# music_badge_v1_2_2017-09-16.net
KiCad netlist of a schematic drawn in EAGLE
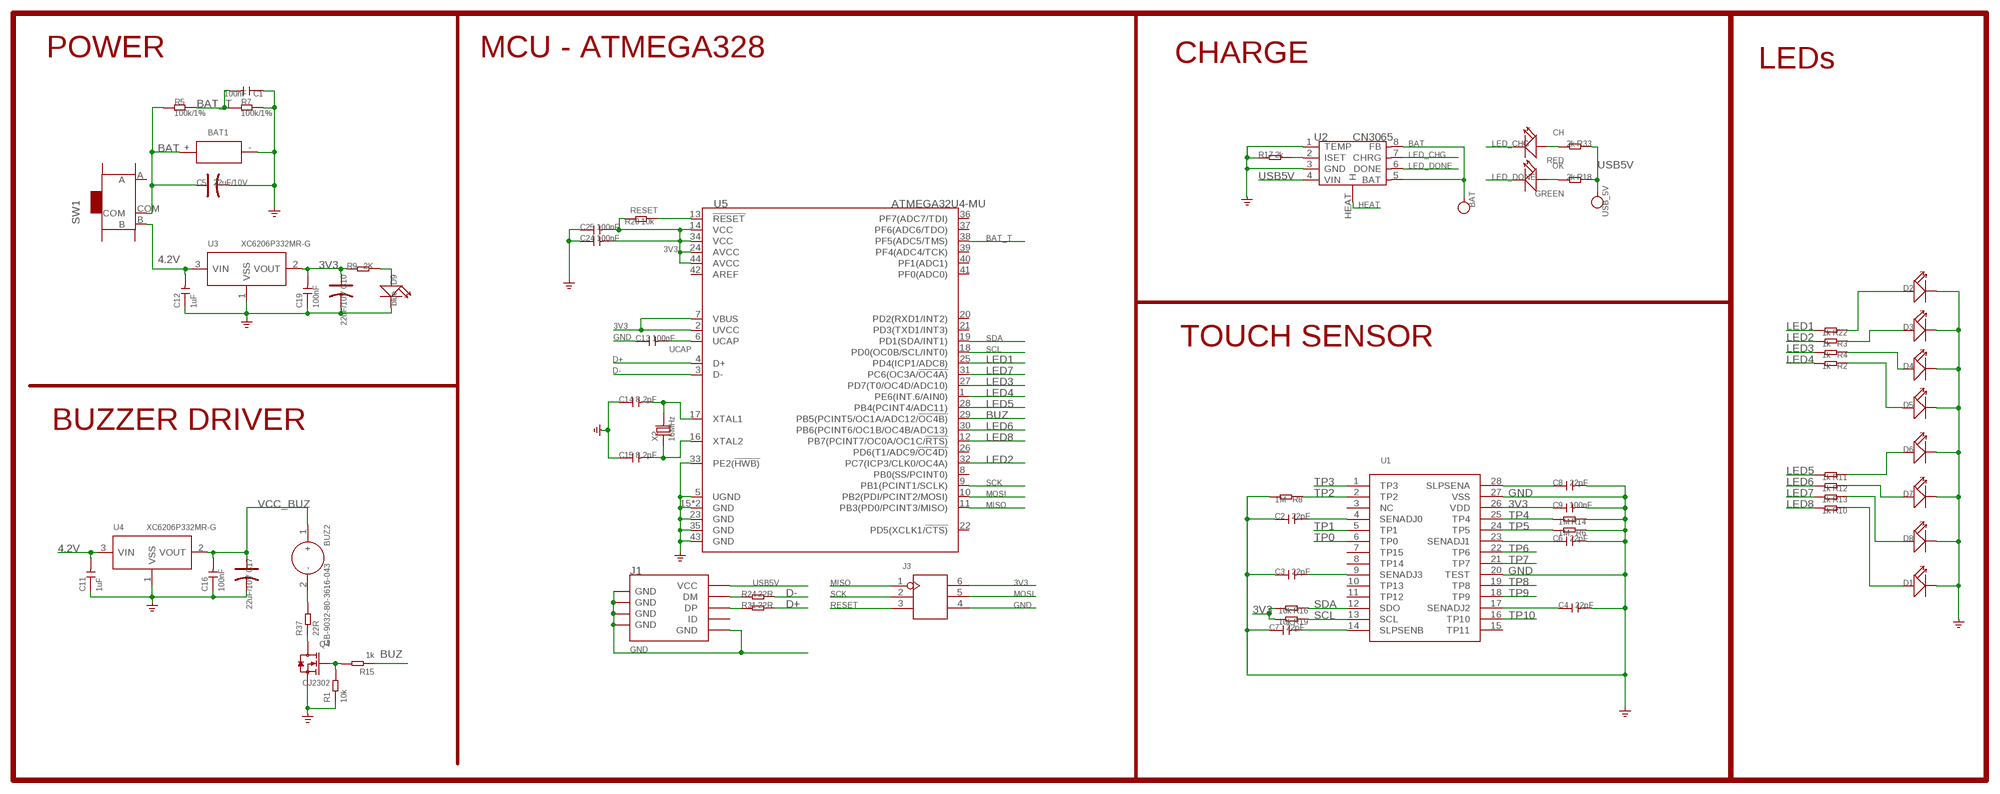
[diagram p0: schematic, sheet 1]

(export (version "E")
  (design (tool "Eeschema 10.0.6"))
  (components
    (comp (ref "BAT")
      (value "TEST-POINT-35")
      (footprint "eagle-import:TP_3535")
      (libsource (lib "eagle-import") (part "TEST-POINT-35"))
    )
    (comp (ref "BAT1")
      (value "HOLDER-BATTERY")
      (footprint "eagle-import:2P-SMD-L28.5_W16_H5.5")
      (libsource (lib "eagle-import") (part "HOLDER-BATTERY"))
    )
    (comp (ref "BUZ2")
      (value "GB-9032-80-3616-043")
      (footprint "eagle-import:BZ2-SMD-9X10.6X3.2MM")
      (libsource (lib "eagle-import") (part "BUZZER-9X3.2MM"))
    )
    (comp (ref "C1")
      (value "100nF")
      (footprint "eagle-import:C0603")
      (libsource (lib "eagle-import") (part "C-0603"))
    )
    (comp (ref "C2")
      (value "22pF")
      (footprint "eagle-import:C0603")
      (libsource (lib "eagle-import") (part "C-0603"))
    )
    (comp (ref "C3")
      (value "22pF")
      (footprint "eagle-import:C0603")
      (libsource (lib "eagle-import") (part "C-0603"))
    )
    (comp (ref "C4")
      (value "22pF")
      (footprint "eagle-import:C0603")
      (libsource (lib "eagle-import") (part "C-0603"))
    )
    (comp (ref "C5")
      (value "22uF/10V")
      (footprint "eagle-import:AVX-B")
      (libsource (lib "eagle-import") (part "CAP-AVX-B"))
    )
    (comp (ref "C6")
      (value "22pF")
      (footprint "eagle-import:C0603")
      (libsource (lib "eagle-import") (part "C-0603"))
    )
    (comp (ref "C7")
      (value "22pF")
      (footprint "eagle-import:C0603")
      (libsource (lib "eagle-import") (part "C-0603"))
    )
    (comp (ref "C8")
      (value "22pF")
      (footprint "eagle-import:C0603")
      (libsource (lib "eagle-import") (part "C-0603"))
    )
    (comp (ref "C9")
      (value "100nF")
      (footprint "eagle-import:C0603")
      (libsource (lib "eagle-import") (part "C-0603"))
    )
    (comp (ref "C10")
      (value "22uF/10V")
      (footprint "eagle-import:AVX-B")
      (libsource (lib "eagle-import") (part "CAP-AVX-B"))
    )
    (comp (ref "C11")
      (value "1uF")
      (footprint "eagle-import:C0603")
      (libsource (lib "eagle-import") (part "CAP-0603"))
    )
    (comp (ref "C12")
      (value "1uF")
      (footprint "eagle-import:C0603")
      (libsource (lib "eagle-import") (part "CAP-0603"))
    )
    (comp (ref "C13")
      (value "100nF")
      (footprint "eagle-import:C0603")
      (libsource (lib "eagle-import") (part "C-0603"))
    )
    (comp (ref "C14")
      (value "8.2pF")
      (footprint "eagle-import:C0603")
      (libsource (lib "eagle-import") (part "C-0603"))
    )
    (comp (ref "C15")
      (value "8.2pF")
      (footprint "eagle-import:C0603")
      (libsource (lib "eagle-import") (part "C-0603"))
    )
    (comp (ref "C16")
      (value "100nF")
      (footprint "eagle-import:C0603")
      (libsource (lib "eagle-import") (part "CAP-0603"))
    )
    (comp (ref "C17")
      (value "22uF/10V")
      (footprint "eagle-import:AVX-B")
      (libsource (lib "eagle-import") (part "CAP-AVX-B"))
    )
    (comp (ref "C19")
      (value "100nF")
      (footprint "eagle-import:C0603")
      (libsource (lib "eagle-import") (part "CAP-0603"))
    )
    (comp (ref "C24")
      (value "100nF")
      (footprint "eagle-import:C0603")
      (libsource (lib "eagle-import") (part "C-0603"))
    )
    (comp (ref "C25")
      (value "100nF")
      (footprint "eagle-import:C0603")
      (libsource (lib "eagle-import") (part "C-0603"))
    )
    (comp (ref "CH")
      (value "RED")
      (footprint "eagle-import:LED-0603")
      (libsource (lib "eagle-import") (part "Discrete-new_LED'0603'"))
    )
    (comp (ref "D1")
      (value "LED-3MM")
      (footprint "eagle-import:LED-2P-2.54-3MM")
      (libsource (lib "eagle-import") (part "LED-3MM"))
    )
    (comp (ref "D2")
      (value "LED-3MM")
      (footprint "eagle-import:LED-2P-2.54-3MM")
      (libsource (lib "eagle-import") (part "LED-3MM"))
    )
    (comp (ref "D3")
      (value "LED-3MM")
      (footprint "eagle-import:LED-2P-2.54-3MM")
      (libsource (lib "eagle-import") (part "LED-3MM"))
    )
    (comp (ref "D4")
      (value "LED-3MM")
      (footprint "eagle-import:LED-2P-2.54-3MM")
      (libsource (lib "eagle-import") (part "LED-3MM"))
    )
    (comp (ref "D5")
      (value "LED-3MM")
      (footprint "eagle-import:LED-2P-2.54-3MM")
      (libsource (lib "eagle-import") (part "LED-3MM"))
    )
    (comp (ref "D6")
      (value "LED-3MM")
      (footprint "eagle-import:LED-2P-2.54-3MM")
      (libsource (lib "eagle-import") (part "LED-3MM"))
    )
    (comp (ref "D7")
      (value "LED-3MM")
      (footprint "eagle-import:LED-2P-2.54-3MM")
      (libsource (lib "eagle-import") (part "LED-3MM"))
    )
    (comp (ref "D8")
      (value "LED-3MM")
      (footprint "eagle-import:LED-2P-2.54-3MM")
      (libsource (lib "eagle-import") (part "LED-3MM"))
    )
    (comp (ref "D9")
      (value "blue")
      (footprint "eagle-import:LED-0603@1")
      (libsource (lib "eagle-import") (part "LED'0603'"))
    )
    (comp (ref "J1")
      (value "USB-MINIUSB-5P-MICRO")
      (footprint "eagle-import:MICRO-USB")
      (libsource (lib "eagle-import") (part "USB-MINIUSB-5P-MICRO"))
    )
    (comp (ref "J3")
      (value "HEADER-2X3P-2.0-1.143")
      (footprint "eagle-import:H2X3-SMD-2.0(1.143)")
      (libsource (lib "eagle-import") (part "HEADER-2X3P-2.0-1.143"))
    )
    (comp (ref "OK")
      (value "GREEN")
      (footprint "eagle-import:LED-0603")
      (libsource (lib "eagle-import") (part "Discrete-new_LED'0603'"))
    )
    (comp (ref "Q4")
      (value "CJ2302")
      (footprint "eagle-import:SOT-23")
      (libsource (lib "eagle-import") (part "MOSFET-N'SOT23'"))
    )
    (comp (ref "R1")
      (value "10k")
      (footprint "eagle-import:R0603")
      (libsource (lib "eagle-import") (part "RES-0603"))
    )
    (comp (ref "R2")
      (value "1k")
      (footprint "eagle-import:R0603")
      (libsource (lib "eagle-import") (part "R-0603"))
    )
    (comp (ref "R3")
      (value "1k")
      (footprint "eagle-import:R0603")
      (libsource (lib "eagle-import") (part "R-0603"))
    )
    (comp (ref "R4")
      (value "1k")
      (footprint "eagle-import:R0603")
      (libsource (lib "eagle-import") (part "R-0603"))
    )
    (comp (ref "R5")
      (value "100k/1%")
      (footprint "eagle-import:R0603")
      (libsource (lib "eagle-import") (part "R-0603"))
    )
    (comp (ref "R6")
      (value "1M")
      (footprint "eagle-import:R0603")
      (libsource (lib "eagle-import") (part "R-0603"))
    )
    (comp (ref "R7")
      (value "100k/1%")
      (footprint "eagle-import:R0603")
      (libsource (lib "eagle-import") (part "R-0603"))
    )
    (comp (ref "R8")
      (value "1M")
      (footprint "eagle-import:R0603")
      (libsource (lib "eagle-import") (part "R-0603"))
    )
    (comp (ref "R9")
      (value "2K")
      (footprint "eagle-import:R0603")
      (libsource (lib "eagle-import") (part "R-0603"))
    )
    (comp (ref "R10")
      (value "1k")
      (footprint "eagle-import:R0603")
      (libsource (lib "eagle-import") (part "R-0603"))
    )
    (comp (ref "R11")
      (value "1k")
      (footprint "eagle-import:R0603")
      (libsource (lib "eagle-import") (part "R-0603"))
    )
    (comp (ref "R12")
      (value "1k")
      (footprint "eagle-import:R0603")
      (libsource (lib "eagle-import") (part "R-0603"))
    )
    (comp (ref "R13")
      (value "1k")
      (footprint "eagle-import:R0603")
      (libsource (lib "eagle-import") (part "R-0603"))
    )
    (comp (ref "R14")
      (value "1M")
      (footprint "eagle-import:R0603")
      (libsource (lib "eagle-import") (part "R-0603"))
    )
    (comp (ref "R15")
      (value "1k")
      (footprint "eagle-import:R0603")
      (libsource (lib "eagle-import") (part "RES-0603"))
    )
    (comp (ref "R16")
      (value "10k")
      (footprint "eagle-import:R0603")
      (libsource (lib "eagle-import") (part "R-0603"))
    )
    (comp (ref "R17")
      (value "2k")
      (footprint "eagle-import:R0603")
      (libsource (lib "eagle-import") (part "R-0603"))
    )
    (comp (ref "R18")
      (value "2k")
      (footprint "eagle-import:R0603")
      (libsource (lib "eagle-import") (part "R-0603"))
    )
    (comp (ref "R19")
      (value "10k")
      (footprint "eagle-import:R0603")
      (libsource (lib "eagle-import") (part "R-0603"))
    )
    (comp (ref "R20")
      (value "10k")
      (footprint "eagle-import:R0603")
      (libsource (lib "eagle-import") (part "R-0603"))
    )
    (comp (ref "R22")
      (value "1k")
      (footprint "eagle-import:R0603")
      (libsource (lib "eagle-import") (part "R-0603"))
    )
    (comp (ref "R24")
      (value "22R")
      (footprint "eagle-import:R0603")
      (libsource (lib "eagle-import") (part "R-0603"))
    )
    (comp (ref "R31")
      (value "22R")
      (footprint "eagle-import:R0603")
      (libsource (lib "eagle-import") (part "R-0603"))
    )
    (comp (ref "R33")
      (value "2k")
      (footprint "eagle-import:R0603")
      (libsource (lib "eagle-import") (part "R-0603"))
    )
    (comp (ref "R37")
      (value "22R")
      (footprint "eagle-import:R0603")
      (libsource (lib "eagle-import") (part "RES-0603"))
    )
    (comp (ref "SW1")
      (value "SWITCH-3P-SMD-6.6X2.8")
      (footprint "eagle-import:3P-SMD-2CH-6.6X2.8-REINFORCE")
      (libsource (lib "eagle-import") (part "SWITCH-3P-SMD-6.6X2.8"))
    )
    (comp (ref "U1")
      (value "TTP229-BSF")
      (footprint "eagle-import:SSOP28-0.635-10X4MM")
      (libsource (lib "eagle-import") (part "TTP229-BSF"))
    )
    (comp (ref "U2")
      (value "CN3065")
      (footprint "eagle-import:DFN8")
      (libsource (lib "eagle-import") (part "CN3065-DFN8"))
    )
    (comp (ref "U3")
      (value "XC6206P332MR-G")
      (footprint "eagle-import:SOT-23")
      (libsource (lib "eagle-import") (part "PMIC-XC6206PMR"))
    )
    (comp (ref "U4")
      (value "XC6206P332MR-G")
      (footprint "eagle-import:SOT-23")
      (libsource (lib "eagle-import") (part "PMIC-XC6206PMR"))
    )
    (comp (ref "U5")
      (value "ATMEGA32U4-MU")
      (footprint "eagle-import:QFN44")
      (libsource (lib "eagle-import") (part "ATMEGA32U4-MU"))
    )
    (comp (ref "USB_5V")
      (value "TEST-POINT-35")
      (footprint "eagle-import:TP_3535")
      (libsource (lib "eagle-import") (part "TEST-POINT-35"))
    )
    (comp (ref "X2")
      (value "16MHz")
      (footprint "eagle-import:2P-SMD-5X3.2")
      (libsource (lib "eagle-import") (part "CRYSTAL'5032'"))
    )
  )
  (nets
    (net (code "1") (name "/3V3") (class "Default")
      (node (ref "C10") (pin "+") (pinfunction "+_+") (pintype "passive"))
      (node (ref "C19") (pin "2") (pinfunction "2_2") (pintype "passive"))
      (node (ref "C24") (pin "2") (pinfunction "2_2") (pintype "passive"))
      (node (ref "C25") (pin "2") (pinfunction "2_2") (pintype "passive"))
      (node (ref "C9") (pin "1") (pinfunction "1_1") (pintype "passive"))
      (node (ref "J3") (pin "6") (pinfunction "6_6") (pintype "bidirectional"))
      (node (ref "R16") (pin "2") (pinfunction "2_2") (pintype "passive"))
      (node (ref "R19") (pin "2") (pinfunction "2_2") (pintype "passive"))
      (node (ref "R20") (pin "1") (pinfunction "1_1") (pintype "passive"))
      (node (ref "R9") (pin "1") (pinfunction "1_1") (pintype "passive"))
      (node (ref "U1") (pin "26") (pinfunction "VDD_26") (pintype "bidirectional"))
      (node (ref "U3") (pin "2") (pinfunction "VOUT_2") (pintype "bidirectional"))
      (node (ref "U5") (pin "14") (pinfunction "VCC_14") (pintype "bidirectional"))
      (node (ref "U5") (pin "2") (pinfunction "UVCC_2") (pintype "bidirectional"))
      (node (ref "U5") (pin "24") (pinfunction "AVCC_24") (pintype "bidirectional"))
      (node (ref "U5") (pin "34") (pinfunction "VCC_34") (pintype "bidirectional"))
      (node (ref "U5") (pin "44") (pinfunction "AVCC_44") (pintype "bidirectional"))
      (node (ref "U5") (pin "7") (pinfunction "VBUS_7") (pintype "bidirectional"))
    )
    (net (code "2") (name "/4.2V") (class "Default")
      (node (ref "C11") (pin "2") (pinfunction "2_2") (pintype "passive"))
      (node (ref "C12") (pin "2") (pinfunction "2_2") (pintype "passive"))
      (node (ref "SW1") (pin "B") (pinfunction "B_B") (pintype "bidirectional"))
      (node (ref "U3") (pin "3") (pinfunction "VIN_3") (pintype "bidirectional"))
      (node (ref "U4") (pin "3") (pinfunction "VIN_3") (pintype "bidirectional"))
    )
    (net (code "3") (name "/BAT") (class "Default")
      (node (ref "BAT") (pin "T") (pinfunction "T_T") (pintype "bidirectional"))
      (node (ref "BAT1") (pin "+") (pinfunction "1_+") (pintype "bidirectional"))
      (node (ref "C5") (pin "+") (pinfunction "+_+") (pintype "passive"))
      (node (ref "R5") (pin "1") (pinfunction "1_1") (pintype "passive"))
      (node (ref "SW1") (pin "COM") (pinfunction "COM_COM") (pintype "bidirectional"))
      (node (ref "U2") (pin "5") (pinfunction "BAT_5") (pintype "bidirectional"))
      (node (ref "U2") (pin "8") (pinfunction "FB_8") (pintype "input"))
    )
    (net (code "4") (name "/BAT_T") (class "Default")
      (node (ref "C1") (pin "2") (pinfunction "2_2") (pintype "passive"))
      (node (ref "R5") (pin "2") (pinfunction "2_2") (pintype "passive"))
      (node (ref "R7") (pin "1") (pinfunction "1_1") (pintype "passive"))
      (node (ref "U5") (pin "38") (pinfunction "PF5(ADC5/TMS)_38") (pintype "bidirectional"))
    )
    (net (code "5") (name "/BUZ") (class "Default")
      (node (ref "R15") (pin "1") (pinfunction "1_1") (pintype "passive"))
      (node (ref "U5") (pin "29") (pinfunction "PB5(PCINT5/OC1A/ADC12/~{OC4B})_29") (pintype "bidirectional"))
    )
    (net (code "6") (name "/D+") (class "Default")
      (node (ref "R31") (pin "2") (pinfunction "2_2") (pintype "passive"))
      (node (ref "U5") (pin "4") (pinfunction "D+_4") (pintype "bidirectional"))
    )
    (net (code "7") (name "/D-") (class "Default")
      (node (ref "R24") (pin "2") (pinfunction "2_2") (pintype "passive"))
      (node (ref "U5") (pin "3") (pinfunction "D-_3") (pintype "bidirectional"))
    )
    (net (code "8") (name "/HEAT") (class "Default")
      (node (ref "U2") (pin "HEAT") (pinfunction "H_HEAT") (pintype "bidirectional"))
    )
    (net (code "9") (name "/LED1") (class "Default")
      (node (ref "R22") (pin "2") (pinfunction "2_2") (pintype "passive"))
      (node (ref "U5") (pin "25") (pinfunction "PD4(ICP1/ADC8)_25") (pintype "bidirectional"))
    )
    (net (code "10") (name "/LED2") (class "Default")
      (node (ref "R3") (pin "2") (pinfunction "2_2") (pintype "passive"))
      (node (ref "U5") (pin "32") (pinfunction "PC7(ICP3/CLK0/OC4A)_32") (pintype "bidirectional"))
    )
    (net (code "11") (name "/LED3") (class "Default")
      (node (ref "R4") (pin "2") (pinfunction "2_2") (pintype "passive"))
      (node (ref "U5") (pin "27") (pinfunction "PD7(T0/OC4D/ADC10)_27") (pintype "bidirectional"))
    )
    (net (code "12") (name "/LED4") (class "Default")
      (node (ref "R2") (pin "2") (pinfunction "2_2") (pintype "passive"))
      (node (ref "U5") (pin "1") (pinfunction "PE6(INT.6/AIN0)_1") (pintype "bidirectional"))
    )
    (net (code "13") (name "/LED5") (class "Default")
      (node (ref "R11") (pin "2") (pinfunction "2_2") (pintype "passive"))
      (node (ref "U5") (pin "28") (pinfunction "PB4(PCINT4/ADC11)_28") (pintype "bidirectional"))
    )
    (net (code "14") (name "/LED6") (class "Default")
      (node (ref "R12") (pin "2") (pinfunction "2_2") (pintype "passive"))
      (node (ref "U5") (pin "30") (pinfunction "PB6(PCINT6/OC1B/OC4B/ADC13)_30") (pintype "bidirectional"))
    )
    (net (code "15") (name "/LED7") (class "Default")
      (node (ref "R13") (pin "2") (pinfunction "2_2") (pintype "passive"))
      (node (ref "U5") (pin "31") (pinfunction "PC6(OC3A/~{OC4A})_31") (pintype "bidirectional"))
    )
    (net (code "16") (name "/LED8") (class "Default")
      (node (ref "R10") (pin "2") (pinfunction "2_2") (pintype "passive"))
      (node (ref "U5") (pin "12") (pinfunction "PB7(PCINT7/OC0A/OC1C/~{RTS})_12") (pintype "bidirectional"))
    )
    (net (code "17") (name "/LED_CHG") (class "Default")
      (node (ref "CH") (pin "-") (pinfunction "-_-") (pintype "passive"))
      (node (ref "U2") (pin "7") (pinfunction "CHRG_7") (pintype "bidirectional"))
    )
    (net (code "18") (name "/LED_DONE") (class "Default")
      (node (ref "OK") (pin "-") (pinfunction "-_-") (pintype "passive"))
      (node (ref "U2") (pin "6") (pinfunction "DONE_6") (pintype "bidirectional"))
    )
    (net (code "19") (name "/MISO") (class "Default")
      (node (ref "J3") (pin "1") (pinfunction "1_1") (pintype "bidirectional"))
      (node (ref "U5") (pin "11") (pinfunction "PB3(PD0/PCINT3/MISO)_11") (pintype "bidirectional"))
    )
    (net (code "20") (name "/MOSI") (class "Default")
      (node (ref "J3") (pin "5") (pinfunction "5_5") (pintype "bidirectional"))
      (node (ref "U5") (pin "10") (pinfunction "PB2(PDI/PCINT2/MOSI)_10") (pintype "bidirectional"))
    )
    (net (code "21") (name "/RESET") (class "Default")
      (node (ref "J3") (pin "3") (pinfunction "3_3") (pintype "bidirectional"))
      (node (ref "R20") (pin "2") (pinfunction "2_2") (pintype "passive"))
      (node (ref "U5") (pin "13") (pinfunction "~{RESET}_13") (pintype "bidirectional"))
    )
    (net (code "22") (name "/SCK") (class "Default")
      (node (ref "J3") (pin "2") (pinfunction "2_2") (pintype "bidirectional"))
      (node (ref "U5") (pin "9") (pinfunction "PB1(PCINT1/SCLK)_9") (pintype "bidirectional"))
    )
    (net (code "23") (name "/SCL") (class "Default")
      (node (ref "R19") (pin "1") (pinfunction "1_1") (pintype "passive"))
      (node (ref "U1") (pin "13") (pinfunction "SCL_13") (pintype "bidirectional"))
      (node (ref "U5") (pin "18") (pinfunction "PD0(OC0B/SCL/INT0)_18") (pintype "bidirectional"))
    )
    (net (code "24") (name "/SDA") (class "Default")
      (node (ref "R16") (pin "1") (pinfunction "1_1") (pintype "passive"))
      (node (ref "U1") (pin "12") (pinfunction "SDO_12") (pintype "bidirectional"))
      (node (ref "U5") (pin "19") (pinfunction "PD1(SDA/INT1)_19") (pintype "bidirectional"))
    )
    (net (code "25") (name "/TP0") (class "Default")
      (node (ref "U1") (pin "6") (pinfunction "TP0_6") (pintype "bidirectional"))
    )
    (net (code "26") (name "/TP1") (class "Default")
      (node (ref "U1") (pin "5") (pinfunction "TP1_5") (pintype "bidirectional"))
    )
    (net (code "27") (name "/TP2") (class "Default")
      (node (ref "R8") (pin "1") (pinfunction "1_1") (pintype "passive"))
      (node (ref "U1") (pin "2") (pinfunction "TP2_2") (pintype "bidirectional"))
    )
    (net (code "28") (name "/TP3") (class "Default")
      (node (ref "U1") (pin "1") (pinfunction "TP3_1") (pintype "bidirectional"))
    )
    (net (code "29") (name "/TP4") (class "Default")
      (node (ref "R14") (pin "2") (pinfunction "2_2") (pintype "passive"))
      (node (ref "U1") (pin "25") (pinfunction "TP4_25") (pintype "bidirectional"))
    )
    (net (code "30") (name "/TP5") (class "Default")
      (node (ref "R6") (pin "2") (pinfunction "2_2") (pintype "passive"))
      (node (ref "U1") (pin "24") (pinfunction "TP5_24") (pintype "bidirectional"))
    )
    (net (code "31") (name "/TP6") (class "Default")
      (node (ref "U1") (pin "22") (pinfunction "TP6_22") (pintype "bidirectional"))
    )
    (net (code "32") (name "/TP7") (class "Default")
      (node (ref "U1") (pin "21") (pinfunction "TP7_21") (pintype "bidirectional"))
    )
    (net (code "33") (name "/TP8") (class "Default")
      (node (ref "U1") (pin "19") (pinfunction "TP8_19") (pintype "bidirectional"))
    )
    (net (code "34") (name "/TP9") (class "Default")
      (node (ref "U1") (pin "18") (pinfunction "TP9_18") (pintype "bidirectional"))
    )
    (net (code "35") (name "/TP10") (class "Default")
      (node (ref "U1") (pin "16") (pinfunction "TP10_16") (pintype "bidirectional"))
    )
    (net (code "36") (name "/UCAP") (class "Default")
      (node (ref "C13") (pin "2") (pinfunction "2_2") (pintype "passive"))
      (node (ref "U5") (pin "6") (pinfunction "UCAP_6") (pintype "bidirectional"))
    )
    (net (code "37") (name "/USB5V") (class "Default")
      (node (ref "J1") (pin "1") (pinfunction "VCC_1") (pintype "bidirectional"))
      (node (ref "R18") (pin "1") (pinfunction "1_1") (pintype "passive"))
      (node (ref "R33") (pin "1") (pinfunction "1_1") (pintype "passive"))
      (node (ref "U2") (pin "4") (pinfunction "VIN_4") (pintype "input"))
      (node (ref "USB_5V") (pin "T") (pinfunction "T_T") (pintype "bidirectional"))
    )
    (net (code "38") (name "/VCC_BUZ") (class "Default")
      (node (ref "BUZ2") (pin "1") (pinfunction "+_1") (pintype "bidirectional"))
      (node (ref "C16") (pin "2") (pinfunction "2_2") (pintype "passive"))
      (node (ref "C17") (pin "+") (pinfunction "+_+") (pintype "passive"))
      (node (ref "U4") (pin "2") (pinfunction "VOUT_2") (pintype "bidirectional"))
    )
    (net (code "39") (name "GND_POWER") (class "Default")
      (node (ref "BAT1") (pin "-") (pinfunction "2_-") (pintype "bidirectional"))
      (node (ref "C1") (pin "1") (pinfunction "1_1") (pintype "passive"))
      (node (ref "C10") (pin "-") (pinfunction "-_-") (pintype "passive"))
      (node (ref "C11") (pin "1") (pinfunction "1_1") (pintype "passive"))
      (node (ref "C12") (pin "1") (pinfunction "1_1") (pintype "passive"))
      (node (ref "C13") (pin "1") (pinfunction "1_1") (pintype "passive"))
      (node (ref "C14") (pin "1") (pinfunction "1_1") (pintype "passive"))
      (node (ref "C15") (pin "1") (pinfunction "1_1") (pintype "passive"))
      (node (ref "C16") (pin "1") (pinfunction "1_1") (pintype "passive"))
      (node (ref "C17") (pin "-") (pinfunction "-_-") (pintype "passive"))
      (node (ref "C19") (pin "1") (pinfunction "1_1") (pintype "passive"))
      (node (ref "C2") (pin "1") (pinfunction "1_1") (pintype "passive"))
      (node (ref "C24") (pin "1") (pinfunction "1_1") (pintype "passive"))
      (node (ref "C25") (pin "1") (pinfunction "1_1") (pintype "passive"))
      (node (ref "C3") (pin "1") (pinfunction "1_1") (pintype "passive"))
      (node (ref "C4") (pin "2") (pinfunction "2_2") (pintype "passive"))
      (node (ref "C5") (pin "-") (pinfunction "-_-") (pintype "passive"))
      (node (ref "C6") (pin "2") (pinfunction "2_2") (pintype "passive"))
      (node (ref "C7") (pin "1") (pinfunction "1_1") (pintype "passive"))
      (node (ref "C8") (pin "2") (pinfunction "2_2") (pintype "passive"))
      (node (ref "C9") (pin "2") (pinfunction "2_2") (pintype "passive"))
      (node (ref "D1") (pin "K") (pinfunction "-_K") (pintype "passive"))
      (node (ref "D2") (pin "K") (pinfunction "-_K") (pintype "passive"))
      (node (ref "D3") (pin "K") (pinfunction "-_K") (pintype "passive"))
      (node (ref "D4") (pin "K") (pinfunction "-_K") (pintype "passive"))
      (node (ref "D5") (pin "K") (pinfunction "-_K") (pintype "passive"))
      (node (ref "D6") (pin "K") (pinfunction "-_K") (pintype "passive"))
      (node (ref "D7") (pin "K") (pinfunction "-_K") (pintype "passive"))
      (node (ref "D8") (pin "K") (pinfunction "-_K") (pintype "passive"))
      (node (ref "D9") (pin "-") (pinfunction "-_-") (pintype "passive"))
      (node (ref "J1") (pin "5") (pinfunction "GND_5") (pintype "bidirectional"))
      (node (ref "J1") (pin "S1") (pinfunction "GND_S1") (pintype "bidirectional"))
      (node (ref "J1") (pin "S2") (pinfunction "GND_S2") (pintype "bidirectional"))
      (node (ref "J1") (pin "S3") (pinfunction "GND_S3") (pintype "bidirectional"))
      (node (ref "J1") (pin "S4") (pinfunction "GND_S4") (pintype "bidirectional"))
      (node (ref "J1") (pin "S5") (pinfunction "GND_S5") (pintype "bidirectional"))
      (node (ref "J1") (pin "S6") (pinfunction "GND_S6") (pintype "bidirectional"))
      (node (ref "J3") (pin "4") (pinfunction "4_4") (pintype "bidirectional"))
      (node (ref "Q4") (pin "2") (pinfunction "S_2") (pintype "passive"))
      (node (ref "R1") (pin "1") (pinfunction "1_1") (pintype "passive"))
      (node (ref "R14") (pin "1") (pinfunction "1_1") (pintype "passive"))
      (node (ref "R17") (pin "1") (pinfunction "1_1") (pintype "passive"))
      (node (ref "R6") (pin "1") (pinfunction "1_1") (pintype "passive"))
      (node (ref "R7") (pin "2") (pinfunction "2_2") (pintype "passive"))
      (node (ref "R8") (pin "2") (pinfunction "2_2") (pintype "passive"))
      (node (ref "U1") (pin "20") (pinfunction "TEST_20") (pintype "bidirectional"))
      (node (ref "U1") (pin "27") (pinfunction "VSS_27") (pintype "bidirectional"))
      (node (ref "U2") (pin "1") (pinfunction "TEMP_1") (pintype "input"))
      (node (ref "U2") (pin "3") (pinfunction "GND_3") (pintype "power_in"))
      (node (ref "U3") (pin "1") (pinfunction "VSS_1") (pintype "bidirectional"))
      (node (ref "U4") (pin "1") (pinfunction "VSS_1") (pintype "bidirectional"))
      (node (ref "U5") (pin "15") (pinfunction "GND_15") (pintype "bidirectional"))
      (node (ref "U5") (pin "23") (pinfunction "GND_23") (pintype "bidirectional"))
      (node (ref "U5") (pin "33") (pinfunction "PE2(~{HWB})_33") (pintype "bidirectional"))
      (node (ref "U5") (pin "35") (pinfunction "GND_35") (pintype "bidirectional"))
      (node (ref "U5") (pin "43") (pinfunction "GND_43") (pintype "bidirectional"))
      (node (ref "U5") (pin "5") (pinfunction "UGND_5") (pintype "bidirectional"))
      (node (ref "U5") (pin "TAB") (pinfunction "GND_TAB") (pintype "bidirectional"))
    )
    (net (code "40") (name "Net-(BUZ2--)") (class "Default")
      (node (ref "BUZ2") (pin "2") (pinfunction "-_2") (pintype "bidirectional"))
      (node (ref "R37") (pin "2") (pinfunction "2_2") (pintype "passive"))
    )
    (net (code "41") (name "Net-(CH-Pad+)") (class "Default")
      (node (ref "CH") (pin "+") (pinfunction "+_+") (pintype "passive"))
      (node (ref "R33") (pin "2") (pinfunction "2_2") (pintype "passive"))
    )
    (net (code "42") (name "Net-(D1-+)") (class "Default")
      (node (ref "D1") (pin "A") (pinfunction "+_A") (pintype "passive"))
      (node (ref "R10") (pin "1") (pinfunction "1_1") (pintype "passive"))
    )
    (net (code "43") (name "Net-(D2-+)") (class "Default")
      (node (ref "D2") (pin "A") (pinfunction "+_A") (pintype "passive"))
      (node (ref "R22") (pin "1") (pinfunction "1_1") (pintype "passive"))
    )
    (net (code "44") (name "Net-(D3-+)") (class "Default")
      (node (ref "D3") (pin "A") (pinfunction "+_A") (pintype "passive"))
      (node (ref "R3") (pin "1") (pinfunction "1_1") (pintype "passive"))
    )
    (net (code "45") (name "Net-(D4-+)") (class "Default")
      (node (ref "D4") (pin "A") (pinfunction "+_A") (pintype "passive"))
      (node (ref "R4") (pin "1") (pinfunction "1_1") (pintype "passive"))
    )
    (net (code "46") (name "Net-(D5-+)") (class "Default")
      (node (ref "D5") (pin "A") (pinfunction "+_A") (pintype "passive"))
      (node (ref "R2") (pin "1") (pinfunction "1_1") (pintype "passive"))
    )
    (net (code "47") (name "Net-(D6-+)") (class "Default")
      (node (ref "D6") (pin "A") (pinfunction "+_A") (pintype "passive"))
      (node (ref "R11") (pin "1") (pinfunction "1_1") (pintype "passive"))
    )
    (net (code "48") (name "Net-(D7-+)") (class "Default")
      (node (ref "D7") (pin "A") (pinfunction "+_A") (pintype "passive"))
      (node (ref "R12") (pin "1") (pinfunction "1_1") (pintype "passive"))
    )
    (net (code "49") (name "Net-(D8-+)") (class "Default")
      (node (ref "D8") (pin "A") (pinfunction "+_A") (pintype "passive"))
      (node (ref "R13") (pin "1") (pinfunction "1_1") (pintype "passive"))
    )
    (net (code "50") (name "Net-(D9-Pad+)") (class "Default")
      (node (ref "D9") (pin "+") (pinfunction "+_+") (pintype "passive"))
      (node (ref "R9") (pin "2") (pinfunction "2_2") (pintype "passive"))
    )
    (net (code "51") (name "Net-(J1-DM)") (class "Default")
      (node (ref "J1") (pin "2") (pinfunction "DM_2") (pintype "bidirectional"))
      (node (ref "R24") (pin "1") (pinfunction "1_1") (pintype "passive"))
    )
    (net (code "52") (name "Net-(J1-DP)") (class "Default")
      (node (ref "J1") (pin "3") (pinfunction "DP_3") (pintype "bidirectional"))
      (node (ref "R31") (pin "1") (pinfunction "1_1") (pintype "passive"))
    )
    (net (code "53") (name "Net-(OK-Pad+)") (class "Default")
      (node (ref "OK") (pin "+") (pinfunction "+_+") (pintype "passive"))
      (node (ref "R18") (pin "2") (pinfunction "2_2") (pintype "passive"))
    )
    (net (code "54") (name "Net-(Q4-D)") (class "Default")
      (node (ref "Q4") (pin "3") (pinfunction "D_3") (pintype "passive"))
      (node (ref "R37") (pin "1") (pinfunction "1_1") (pintype "passive"))
    )
    (net (code "55") (name "Net-(Q4-G)") (class "Default")
      (node (ref "Q4") (pin "1") (pinfunction "G_1") (pintype "passive"))
      (node (ref "R1") (pin "2") (pinfunction "2_2") (pintype "passive"))
      (node (ref "R15") (pin "2") (pinfunction "2_2") (pintype "passive"))
    )
    (net (code "56") (name "Net-(U1-SENADJ0)") (class "Default")
      (node (ref "C2") (pin "2") (pinfunction "2_2") (pintype "passive"))
      (node (ref "U1") (pin "4") (pinfunction "SENADJ0_4") (pintype "bidirectional"))
    )
    (net (code "57") (name "Net-(U1-SENADJ1)") (class "Default")
      (node (ref "C6") (pin "1") (pinfunction "1_1") (pintype "passive"))
      (node (ref "U1") (pin "23") (pinfunction "SENADJ1_23") (pintype "bidirectional"))
    )
    (net (code "58") (name "Net-(U1-SENADJ2)") (class "Default")
      (node (ref "C4") (pin "1") (pinfunction "1_1") (pintype "passive"))
      (node (ref "U1") (pin "17") (pinfunction "SENADJ2_17") (pintype "bidirectional"))
    )
    (net (code "59") (name "Net-(U1-SENADJ3)") (class "Default")
      (node (ref "C3") (pin "2") (pinfunction "2_2") (pintype "passive"))
      (node (ref "U1") (pin "9") (pinfunction "SENADJ3_9") (pintype "bidirectional"))
    )
    (net (code "60") (name "Net-(U1-SLPSENA)") (class "Default")
      (node (ref "C8") (pin "1") (pinfunction "1_1") (pintype "passive"))
      (node (ref "U1") (pin "28") (pinfunction "SLPSENA_28") (pintype "bidirectional"))
    )
    (net (code "61") (name "Net-(U1-SLPSENB)") (class "Default")
      (node (ref "C7") (pin "2") (pinfunction "2_2") (pintype "passive"))
      (node (ref "U1") (pin "14") (pinfunction "SLPSENB_14") (pintype "bidirectional"))
    )
    (net (code "62") (name "Net-(U2-ISET)") (class "Default")
      (node (ref "R17") (pin "2") (pinfunction "2_2") (pintype "passive"))
      (node (ref "U2") (pin "2") (pinfunction "ISET_2") (pintype "bidirectional"))
    )
    (net (code "63") (name "Net-(U5-XTAL1)") (class "Default")
      (node (ref "C14") (pin "2") (pinfunction "2_2") (pintype "passive"))
      (node (ref "U5") (pin "17") (pinfunction "XTAL1_17") (pintype "bidirectional"))
      (node (ref "X2") (pin "2") (pinfunction "2_2") (pintype "passive"))
    )
    (net (code "64") (name "Net-(U5-XTAL2)") (class "Default")
      (node (ref "C15") (pin "2") (pinfunction "2_2") (pintype "passive"))
      (node (ref "U5") (pin "16") (pinfunction "XTAL2_16") (pintype "bidirectional"))
      (node (ref "X2") (pin "1") (pinfunction "1_1") (pintype "passive"))
    )
    (net (code "65") (name "unconnected-(J1-ID-Pad4)") (class "Default")
      (node (ref "J1") (pin "4") (pinfunction "ID_4") (pintype "bidirectional"))
    )
    (net (code "66") (name "unconnected-(SW1-PadA)") (class "Default")
      (node (ref "SW1") (pin "A") (pinfunction "A_A") (pintype "bidirectional"))
    )
    (net (code "67") (name "unconnected-(SW1-PadSS1)") (class "Default")
      (node (ref "SW1") (pin "SS1") (pinfunction "SS1_SS1") (pintype "bidirectional"))
    )
    (net (code "68") (name "unconnected-(SW1-PadSS2)") (class "Default")
      (node (ref "SW1") (pin "SS2") (pinfunction "SS2_SS2") (pintype "bidirectional"))
    )
    (net (code "69") (name "unconnected-(SW1-PadSS3)") (class "Default")
      (node (ref "SW1") (pin "SS3") (pinfunction "SS3_SS3") (pintype "bidirectional"))
    )
    (net (code "70") (name "unconnected-(SW1-PadSS4)") (class "Default")
      (node (ref "SW1") (pin "SS4") (pinfunction "SS4_SS4") (pintype "bidirectional"))
    )
    (net (code "71") (name "unconnected-(U1-NC-Pad3)") (class "Default")
      (node (ref "U1") (pin "3") (pinfunction "NC_3") (pintype "bidirectional"))
    )
    (net (code "72") (name "unconnected-(U1-TP11-Pad15)") (class "Default")
      (node (ref "U1") (pin "15") (pinfunction "TP11_15") (pintype "bidirectional"))
    )
    (net (code "73") (name "unconnected-(U1-TP12-Pad11)") (class "Default")
      (node (ref "U1") (pin "11") (pinfunction "TP12_11") (pintype "bidirectional"))
    )
    (net (code "74") (name "unconnected-(U1-TP13-Pad10)") (class "Default")
      (node (ref "U1") (pin "10") (pinfunction "TP13_10") (pintype "bidirectional"))
    )
    (net (code "75") (name "unconnected-(U1-TP14-Pad8)") (class "Default")
      (node (ref "U1") (pin "8") (pinfunction "TP14_8") (pintype "bidirectional"))
    )
    (net (code "76") (name "unconnected-(U1-TP15-Pad7)") (class "Default")
      (node (ref "U1") (pin "7") (pinfunction "TP15_7") (pintype "bidirectional"))
    )
    (net (code "77") (name "unconnected-(U5-AREF-Pad42)") (class "Default")
      (node (ref "U5") (pin "42") (pinfunction "AREF_42") (pintype "bidirectional"))
    )
    (net (code "78") (name "unconnected-(U5-PB0(SS{slash}PCINT0)-Pad8)") (class "Default")
      (node (ref "U5") (pin "8") (pinfunction "PB0(SS/PCINT0)_8") (pintype "bidirectional"))
    )
    (net (code "79") (name "unconnected-(U5-PD2(RXD1{slash}INT2)-Pad20)") (class "Default")
      (node (ref "U5") (pin "20") (pinfunction "PD2(RXD1/INT2)_20") (pintype "bidirectional"))
    )
    (net (code "80") (name "unconnected-(U5-PD3(TXD1{slash}INT3)-Pad21)") (class "Default")
      (node (ref "U5") (pin "21") (pinfunction "PD3(TXD1/INT3)_21") (pintype "bidirectional"))
    )
    (net (code "81") (name "unconnected-(U5-PD5(XCLK1{slash}~{CTS})-Pad22)") (class "Default")
      (node (ref "U5") (pin "22") (pinfunction "PD5(XCLK1/~{CTS})_22") (pintype "bidirectional"))
    )
    (net (code "82") (name "unconnected-(U5-PD6(T1{slash}ADC9{slash}~{OC4D})-Pad26)") (class "Default")
      (node (ref "U5") (pin "26") (pinfunction "PD6(T1/ADC9/~{OC4D})_26") (pintype "bidirectional"))
    )
    (net (code "83") (name "unconnected-(U5-PF0(ADC0)-Pad41)") (class "Default")
      (node (ref "U5") (pin "41") (pinfunction "PF0(ADC0)_41") (pintype "bidirectional"))
    )
    (net (code "84") (name "unconnected-(U5-PF1(ADC1)-Pad40)") (class "Default")
      (node (ref "U5") (pin "40") (pinfunction "PF1(ADC1)_40") (pintype "bidirectional"))
    )
    (net (code "85") (name "unconnected-(U5-PF4(ADC4{slash}TCK)-Pad39)") (class "Default")
      (node (ref "U5") (pin "39") (pinfunction "PF4(ADC4/TCK)_39") (pintype "bidirectional"))
    )
    (net (code "86") (name "unconnected-(U5-PF6(ADC6{slash}TDO)-Pad37)") (class "Default")
      (node (ref "U5") (pin "37") (pinfunction "PF6(ADC6/TDO)_37") (pintype "bidirectional"))
    )
    (net (code "87") (name "unconnected-(U5-PF7(ADC7{slash}TDI)-Pad36)") (class "Default")
      (node (ref "U5") (pin "36") (pinfunction "PF7(ADC7/TDI)_36") (pintype "bidirectional"))
    )
  )
)
